# mainboard.net
KiCad netlist of a schematic drawn in EAGLE
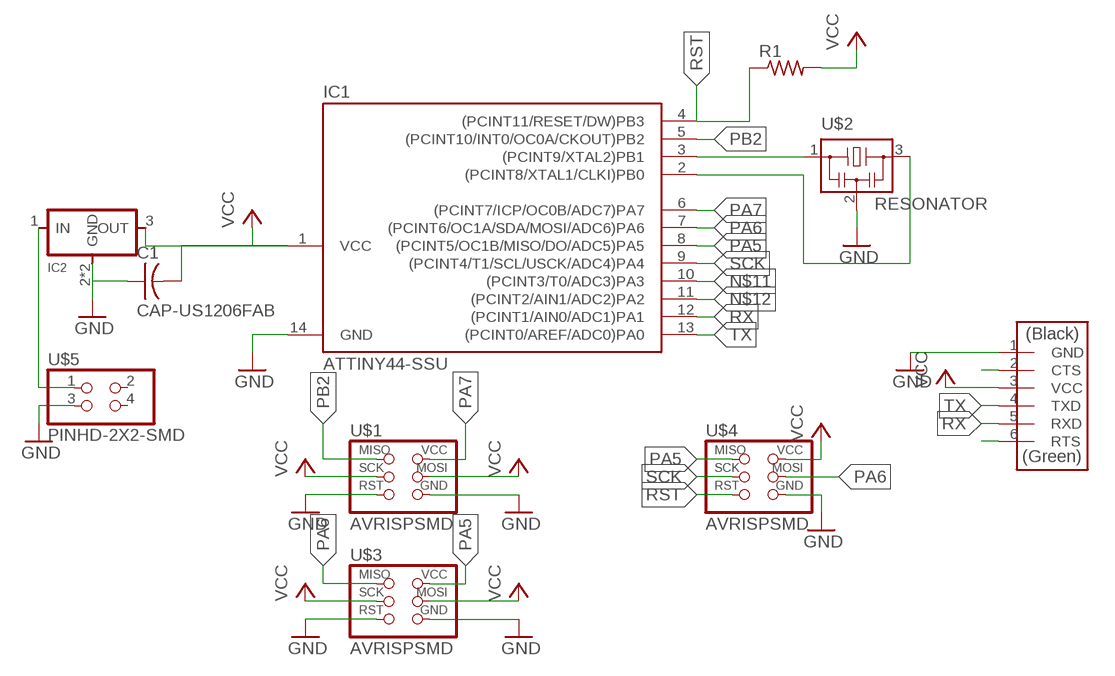
[diagram p0: schematic, sheet 1]

(export (version "E")
  (design (tool "Eeschema 10.0.6"))
  (components
    (comp (ref "C1")
      (value "CAP-US1206FAB")
      (footprint "eagle-import:C1206FAB")
      (libsource (lib "eagle-import") (part "CAP-US1206FAB"))
    )
    (comp (ref "IC1")
      (value "ATTINY44-SSU")
      (footprint "eagle-import:SOIC14")
      (libsource (lib "eagle-import") (part "ATTINY44-SSU"))
    )
    (comp (ref "IC2")
      (value "REGULATORSOT223")
      (footprint "eagle-import:SOT223")
      (libsource (lib "eagle-import") (part "REGULATORSOT223"))
    )
    (comp (ref "R1")
      (value "RES-US1206FAB")
      (footprint "eagle-import:R1206FAB")
      (libsource (lib "eagle-import") (part "RES-US1206FAB"))
    )
    (comp (ref "U$1")
      (value "AVRISPSMD")
      (footprint "eagle-import:2X03SMD")
      (libsource (lib "eagle-import") (part "AVRISPSMD"))
    )
    (comp (ref "U$2")
      (value "RESONATOR")
      (footprint "eagle-import:EFOBM")
      (libsource (lib "eagle-import") (part "RESONATOR"))
    )
    (comp (ref "U$3")
      (value "AVRISPSMD")
      (footprint "eagle-import:2X03SMD")
      (libsource (lib "eagle-import") (part "AVRISPSMD"))
    )
    (comp (ref "U$4")
      (value "AVRISPSMD")
      (footprint "eagle-import:2X03SMD")
      (libsource (lib "eagle-import") (part "AVRISPSMD"))
    )
    (comp (ref "U$5")
      (value "PINHD-2X2-SMD")
      (footprint "eagle-import:2X02SMD")
      (libsource (lib "eagle-import") (part "PINHD-2X2-SMD"))
    )
    (comp (ref "U$6")
      (value "FTDI-SMD-HEADER")
      (footprint "eagle-import:1X06SMD")
      (libsource (lib "eagle-import") (part "FTDI-SMD-HEADER"))
    )
  )
  (nets
    (net (code "1") (name "GND") (class "Default")
      (node (ref "C1") (pin "1") (pinfunction "1_1") (pintype "passive"))
      (node (ref "IC1") (pin "14") (pinfunction "GND_14") (pintype "power_in"))
      (node (ref "IC2") (pin "2") (pinfunction "GND_2") (pintype "bidirectional"))
      (node (ref "IC2") (pin "4") (pinfunction "GND_4") (pintype "bidirectional"))
      (node (ref "U$1") (pin "5") (pinfunction "RST_5") (pintype "passive"))
      (node (ref "U$1") (pin "6") (pinfunction "GND_6") (pintype "passive"))
      (node (ref "U$2") (pin "2") (pinfunction "2_2") (pintype "passive"))
      (node (ref "U$3") (pin "5") (pinfunction "RST_5") (pintype "passive"))
      (node (ref "U$3") (pin "6") (pinfunction "GND_6") (pintype "passive"))
      (node (ref "U$4") (pin "6") (pinfunction "GND_6") (pintype "passive"))
      (node (ref "U$5") (pin "3") (pinfunction "3_3") (pintype "passive"))
      (node (ref "U$6") (pin "1") (pinfunction "GND_1") (pintype "bidirectional"))
    )
    (net (code "2") (name "N$11") (class "Default")
      (node (ref "IC1") (pin "10") (pinfunction "(PCINT3/T0/ADC3)PA3_10") (pintype "bidirectional"))
    )
    (net (code "3") (name "N$12") (class "Default")
      (node (ref "IC1") (pin "11") (pinfunction "(PCINT2/AIN1/ADC2)PA2_11") (pintype "bidirectional"))
    )
    (net (code "4") (name "Net-(IC1-(PCINT8{slash}XTAL1{slash}CLKI)PB0)") (class "Default")
      (node (ref "IC1") (pin "2") (pinfunction "(PCINT8/XTAL1/CLKI)PB0_2") (pintype "bidirectional"))
      (node (ref "U$2") (pin "3") (pinfunction "3_3") (pintype "passive"))
    )
    (net (code "5") (name "Net-(IC1-(PCINT9{slash}XTAL2)PB1)") (class "Default")
      (node (ref "IC1") (pin "3") (pinfunction "(PCINT9/XTAL2)PB1_3") (pintype "bidirectional"))
      (node (ref "U$2") (pin "1") (pinfunction "1_1") (pintype "passive"))
    )
    (net (code "6") (name "Net-(IC2-IN)") (class "Default")
      (node (ref "IC2") (pin "1") (pinfunction "IN_1") (pintype "bidirectional"))
      (node (ref "U$5") (pin "1") (pinfunction "1_1") (pintype "passive"))
    )
    (net (code "7") (name "PA5") (class "Default")
      (node (ref "IC1") (pin "8") (pinfunction "(PCINT5/OC1B/MISO/DO/ADC5)PA5_8") (pintype "bidirectional"))
      (node (ref "U$3") (pin "2") (pinfunction "VCC_2") (pintype "passive"))
      (node (ref "U$4") (pin "1") (pinfunction "MISO_1") (pintype "passive"))
    )
    (net (code "8") (name "PA6") (class "Default")
      (node (ref "IC1") (pin "7") (pinfunction "(PCINT6/OC1A/SDA/MOSI/ADC6)PA6_7") (pintype "bidirectional"))
      (node (ref "U$3") (pin "1") (pinfunction "MISO_1") (pintype "passive"))
      (node (ref "U$4") (pin "4") (pinfunction "MOSI_4") (pintype "passive"))
    )
    (net (code "9") (name "PA7") (class "Default")
      (node (ref "IC1") (pin "6") (pinfunction "(PCINT7/ICP/OC0B/ADC7)PA7_6") (pintype "bidirectional"))
      (node (ref "U$1") (pin "2") (pinfunction "VCC_2") (pintype "passive"))
    )
    (net (code "10") (name "PB2") (class "Default")
      (node (ref "IC1") (pin "5") (pinfunction "(PCINT10/INT0/OC0A/CKOUT)PB2_5") (pintype "bidirectional"))
      (node (ref "U$1") (pin "1") (pinfunction "MISO_1") (pintype "passive"))
    )
    (net (code "11") (name "RST") (class "Default")
      (node (ref "IC1") (pin "4") (pinfunction "(PCINT11/RESET/DW)PB3_4") (pintype "bidirectional"))
      (node (ref "R1") (pin "1") (pinfunction "1_1") (pintype "passive"))
      (node (ref "U$4") (pin "5") (pinfunction "RST_5") (pintype "passive"))
    )
    (net (code "12") (name "RX") (class "Default")
      (node (ref "IC1") (pin "12") (pinfunction "(PCINT1/AIN0/ADC1)PA1_12") (pintype "bidirectional"))
      (node (ref "U$6") (pin "5") (pinfunction "RXD_5") (pintype "bidirectional"))
    )
    (net (code "13") (name "SCK") (class "Default")
      (node (ref "IC1") (pin "9") (pinfunction "(PCINT4/T1/SCL/USCK/ADC4)PA4_9") (pintype "bidirectional"))
      (node (ref "U$4") (pin "3") (pinfunction "SCK_3") (pintype "passive"))
    )
    (net (code "14") (name "TX") (class "Default")
      (node (ref "IC1") (pin "13") (pinfunction "(PCINT0/AREF/ADC0)PA0_13") (pintype "bidirectional"))
      (node (ref "U$6") (pin "4") (pinfunction "TXD_4") (pintype "bidirectional"))
    )
    (net (code "15") (name "VCC") (class "Default")
      (node (ref "C1") (pin "2") (pinfunction "2_2") (pintype "passive"))
      (node (ref "IC1") (pin "1") (pinfunction "VCC_1") (pintype "power_in"))
      (node (ref "IC2") (pin "3") (pinfunction "OUT_3") (pintype "bidirectional"))
      (node (ref "R1") (pin "2") (pinfunction "2_2") (pintype "passive"))
      (node (ref "U$1") (pin "3") (pinfunction "SCK_3") (pintype "passive"))
      (node (ref "U$1") (pin "4") (pinfunction "MOSI_4") (pintype "passive"))
      (node (ref "U$3") (pin "3") (pinfunction "SCK_3") (pintype "passive"))
      (node (ref "U$3") (pin "4") (pinfunction "MOSI_4") (pintype "passive"))
      (node (ref "U$4") (pin "2") (pinfunction "VCC_2") (pintype "passive"))
      (node (ref "U$6") (pin "3") (pinfunction "VCC_3") (pintype "bidirectional"))
    )
    (net (code "16") (name "unconnected-(U$5-Pad2)") (class "Default")
      (node (ref "U$5") (pin "2") (pinfunction "2_2") (pintype "passive"))
    )
    (net (code "17") (name "unconnected-(U$5-Pad4)") (class "Default")
      (node (ref "U$5") (pin "4") (pinfunction "4_4") (pintype "passive"))
    )
    (net (code "18") (name "unconnected-(U$6-CTS-Pad2)") (class "Default")
      (node (ref "U$6") (pin "2") (pinfunction "CTS_2") (pintype "bidirectional"))
    )
    (net (code "19") (name "unconnected-(U$6-RTS-Pad6)") (class "Default")
      (node (ref "U$6") (pin "6") (pinfunction "RTS_6") (pintype "bidirectional"))
    )
  )
)
